# TURBIDITY_SENSOR.net
KiCad netlist of a schematic drawn in EAGLE
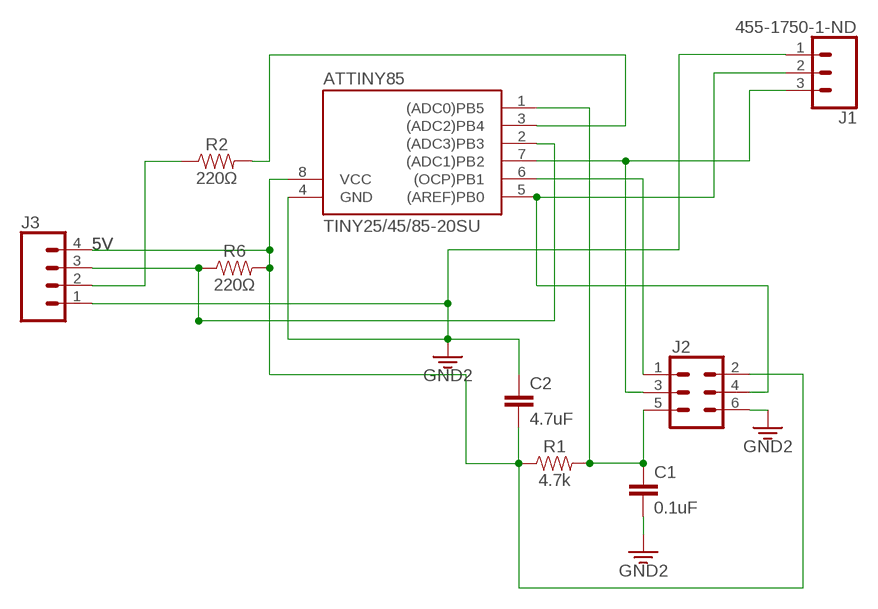
[diagram p0: schematic, sheet 1]

(export (version "E")
  (design (tool "Eeschema 10.0.6"))
  (components
    (comp (ref "ATTINY85")
      (value "TINY25/45/85-20SU")
      (footprint "eagle-import:SOIC8")
      (libsource (lib "eagle-import") (part "TINY25/45/85-20SU"))
    )
    (comp (ref "C1")
      (value "0.1uF")
      (footprint "eagle-import:0603")
      (libsource (lib "eagle-import") (part "0.1UF-0603-25V-(+80/-20%)"))
    )
    (comp (ref "C2")
      (value "4.7uF")
      (footprint "eagle-import:1206")
      (libsource (lib "eagle-import") (part "4.7UF-1206-16V-(+80/-20%)"))
    )
    (comp (ref "J1")
      (value "455-1750-1-ND")
      (footprint "eagle-import:1X03")
      (libsource (lib "eagle-import") (part "CONN_03"))
    )
    (comp (ref "J2")
      (value "CONN_03X22X3_SILK_MALE_PTH")
      (footprint "eagle-import:2X3")
      (libsource (lib "eagle-import") (part "CONN_03X22X3_SILK_MALE_PTH"))
    )
    (comp (ref "J3")
      (value "CONN_04")
      (footprint "eagle-import:1X04")
      (libsource (lib "eagle-import") (part "CONN_04"))
    )
    (comp (ref "R1")
      (value "4.7k")
      (footprint "eagle-import:0603")
      (libsource (lib "eagle-import") (part "4.7KOHM-0603-1/10W-1%"))
    )
    (comp (ref "R2")
      (value "220Ω")
      (footprint "eagle-import:0603")
      (libsource (lib "eagle-import") (part "220OHM-0603-1/10W-1%"))
    )
    (comp (ref "R6")
      (value "220Ω")
      (footprint "eagle-import:0603")
      (libsource (lib "eagle-import") (part "220OHM-0603-1/10W-1%"))
    )
  )
  (nets
    (net (code "1") (name "/5V") (class "Default")
      (node (ref "ATTINY85") (pin "8") (pinfunction "VCC_8") (pintype "power_in"))
      (node (ref "C2") (pin "2") (pinfunction "2_2") (pintype "passive"))
      (node (ref "J2") (pin "2") (pinfunction "2_2") (pintype "bidirectional"))
      (node (ref "J3") (pin "4") (pinfunction "4_4") (pintype "passive"))
      (node (ref "R1") (pin "1") (pinfunction "1_1") (pintype "passive"))
      (node (ref "R6") (pin "2") (pinfunction "2_2") (pintype "passive"))
    )
    (net (code "2") (name "GND2") (class "Default")
      (node (ref "ATTINY85") (pin "4") (pinfunction "GND_4") (pintype "power_in"))
      (node (ref "C1") (pin "2") (pinfunction "2_2") (pintype "passive"))
      (node (ref "C2") (pin "1") (pinfunction "1_1") (pintype "passive"))
      (node (ref "J1") (pin "1") (pinfunction "1_1") (pintype "passive"))
      (node (ref "J2") (pin "6") (pinfunction "6_6") (pintype "bidirectional"))
      (node (ref "J3") (pin "1") (pinfunction "1_1") (pintype "passive"))
    )
    (net (code "3") (name "Net-(ATTINY85-(ADC0)PB5)") (class "Default")
      (node (ref "ATTINY85") (pin "1") (pinfunction "(ADC0)PB5_1") (pintype "bidirectional"))
      (node (ref "C1") (pin "1") (pinfunction "1_1") (pintype "passive"))
      (node (ref "J2") (pin "5") (pinfunction "5_5") (pintype "bidirectional"))
      (node (ref "R1") (pin "2") (pinfunction "2_2") (pintype "passive"))
    )
    (net (code "4") (name "Net-(ATTINY85-(ADC1)PB2)") (class "Default")
      (node (ref "ATTINY85") (pin "7") (pinfunction "(ADC1)PB2_7") (pintype "bidirectional"))
      (node (ref "J1") (pin "3") (pinfunction "3_3") (pintype "passive"))
      (node (ref "J2") (pin "3") (pinfunction "3_3") (pintype "bidirectional"))
    )
    (net (code "5") (name "Net-(ATTINY85-(ADC2)PB4)") (class "Default")
      (node (ref "ATTINY85") (pin "3") (pinfunction "(ADC2)PB4_3") (pintype "bidirectional"))
      (node (ref "R2") (pin "2") (pinfunction "2_2") (pintype "passive"))
    )
    (net (code "6") (name "Net-(ATTINY85-(ADC3)PB3)") (class "Default")
      (node (ref "ATTINY85") (pin "2") (pinfunction "(ADC3)PB3_2") (pintype "bidirectional"))
      (node (ref "J3") (pin "3") (pinfunction "3_3") (pintype "passive"))
      (node (ref "R6") (pin "1") (pinfunction "1_1") (pintype "passive"))
    )
    (net (code "7") (name "Net-(ATTINY85-(AREF)PB0)") (class "Default")
      (node (ref "ATTINY85") (pin "5") (pinfunction "(AREF)PB0_5") (pintype "bidirectional"))
      (node (ref "J1") (pin "2") (pinfunction "2_2") (pintype "passive"))
      (node (ref "J2") (pin "4") (pinfunction "4_4") (pintype "bidirectional"))
    )
    (net (code "8") (name "Net-(ATTINY85-(OCP)PB1)") (class "Default")
      (node (ref "ATTINY85") (pin "6") (pinfunction "(OCP)PB1_6") (pintype "bidirectional"))
      (node (ref "J2") (pin "1") (pinfunction "1_1") (pintype "bidirectional"))
    )
    (net (code "9") (name "Net-(J3-Pad2)") (class "Default")
      (node (ref "J3") (pin "2") (pinfunction "2_2") (pintype "passive"))
      (node (ref "R2") (pin "1") (pinfunction "1_1") (pintype "passive"))
    )
  )
)
